# Mechanics.net
KiCad netlist of a schematic drawn in Altium Designer
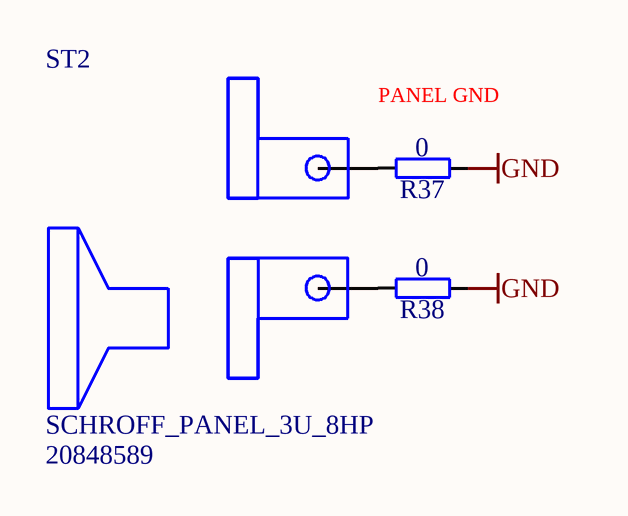
[diagram p0: Mechanics.SchDoc]

(export (version "E")
  (design (tool "Eeschema 10.0.6"))
  (components
    (comp (ref "R37")
      (value "0")
      (footprint "RESC1608X55N")
      (description "Resistor")
      (fields
        (field (name "PART NUMBER") "R0603_0R_JUMPER")
        (field (name "MANUFACTURER") "GENERIC")
        (field (name "AUTHOR") "CERN DEM JLC")
      )
      (libsource (lib "Resistors") (part "Resistor"))
    )
    (comp (ref "R38")
      (value "0")
      (footprint "RESC1608X55N")
      (description "Resistor")
      (fields
        (field (name "PART NUMBER") "R0603_0R_JUMPER")
        (field (name "MANUFACTURER") "GENERIC")
        (field (name "AUTHOR") "CERN DEM JLC")
      )
      (libsource (lib "Resistors") (part "Resistor"))
    )
    (comp (ref "ST2")
      (value "SCHROFF_PANEL_3U_8HP")
      (footprint "SCHROFF_PANEL_3HP_8U_CPCIS_AC_PSU")
      (description "Schroff 8HP 4U EUROCARD Panel with ejector")
      (fields
        (field (name "MANUFACTURER") "Schroff")
        (field (name "MANUFACTURER PART NUMBER") "20848589")
        (field (name "MANUFACTURER PART NUMBER 2") "20848589")
      )
      (libsource (lib "Mechanical") (part "SCHROFF_PANEL_3U_8HP_CPCIS_PSU"))
    )
  )
  (nets
    (net (code "1") (name "GND") (class "Default")
      (node (ref "R37") (pin "1") (pinfunction "1_1") (pintype "passive"))
      (node (ref "R38") (pin "1") (pinfunction "1_1") (pintype "passive"))
    )
    (net (code "2") (name "Net-(R37-Pad2)") (class "Default")
      (node (ref "R37") (pin "2") (pinfunction "2_2") (pintype "passive"))
      (node (ref "ST2") (pin "1") (pinfunction "1_1") (pintype "passive"))
    )
    (net (code "3") (name "Net-(R38-Pad2)") (class "Default")
      (node (ref "R38") (pin "2") (pinfunction "2_2") (pintype "passive"))
      (node (ref "ST2") (pin "0") (pinfunction "0_0") (pintype "passive"))
    )
  )
)
